# LB1_Expansion_Board.net
KiCad netlist of a schematic drawn in EAGLE
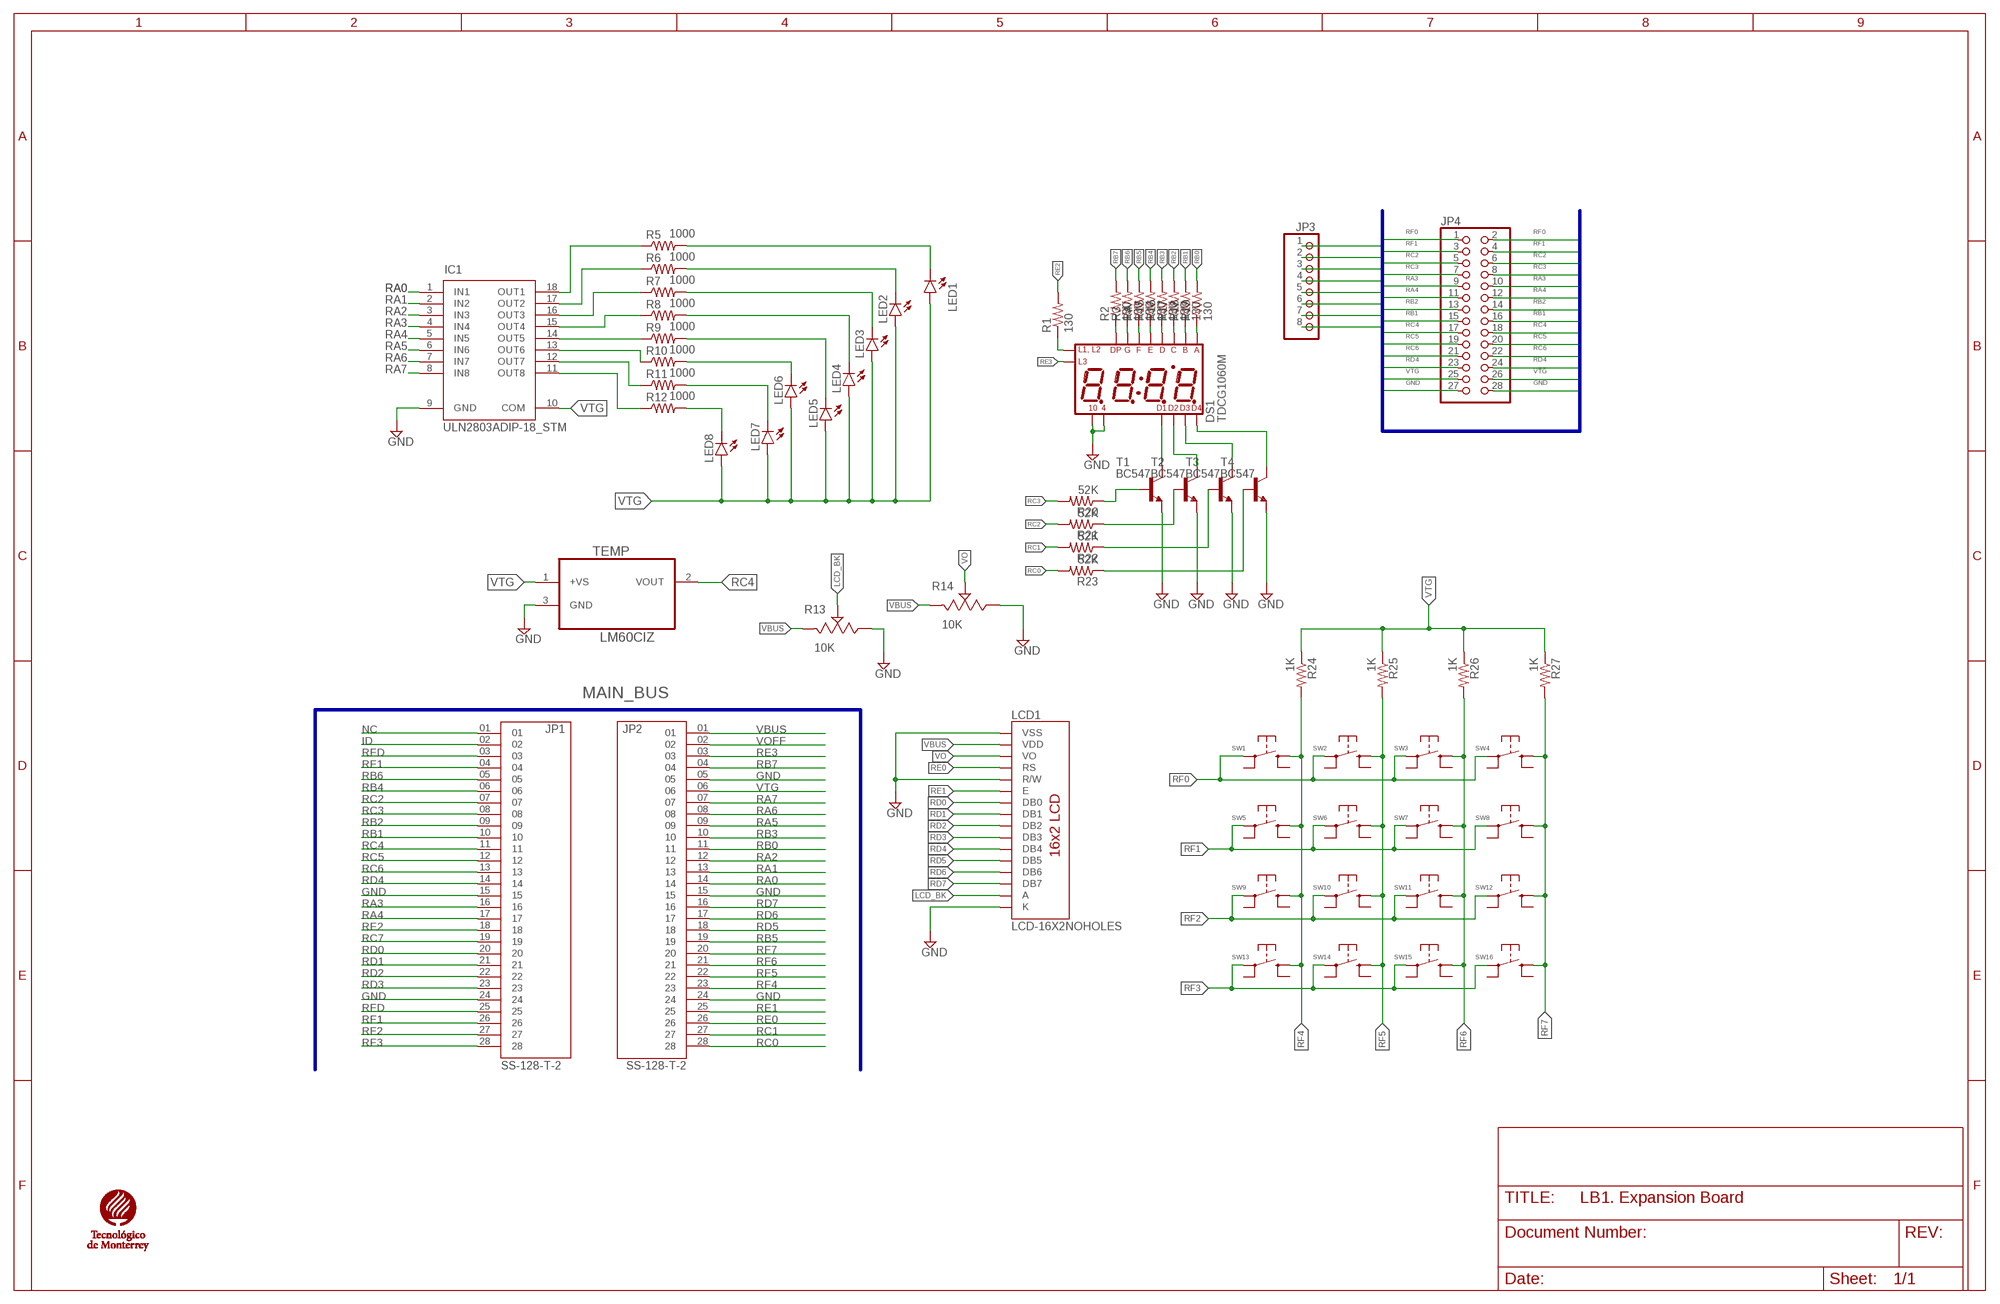
[diagram p0: schematic, sheet 1]

(export (version "E")
  (design (tool "Eeschema 10.0.6"))
  (components
    (comp (ref "DS1")
      (value "TDCG1060M")
      (footprint "eagle-import:DISPLAY_TDCG1060M")
      (fields (field (name "DIGI-KEY_PART_NUMBER") "TDCG1060M-ND") (field (name "MF") "Vishay"))
      (libsource (lib "eagle-import") (part "TDCG1060M"))
    )
    (comp (ref "IC1")
      (value "ULN2803ADIP-18_STM")
      (footprint "eagle-import:DIP-18_STM")
      (fields
        (field (name "MANUFACTURER_PART_NUMBER") "ULN2803A")
        (field (name "COPYRIGHT") "Copyright (C) 2022 Ultra Librarian. All rights reserved.")
      )
      (libsource (lib "eagle-import") (part "ULN2803ADIP-18_STM"))
    )
    (comp (ref "JP1")
      (value "SS-128-T-2")
      (footprint "eagle-import:SAMTEC_SS-128-T-2")
      (fields (field (name "DIGI-KEY_PART_NUMBER") "SAM1117-28-ND") (field (name "MF") "Samtec"))
      (libsource (lib "eagle-import") (part "SS-128-T-2"))
    )
    (comp (ref "JP2")
      (value "SS-128-T-2")
      (footprint "eagle-import:SAMTEC_SS-128-T-2")
      (fields (field (name "DIGI-KEY_PART_NUMBER") "SAM1117-28-ND") (field (name "MF") "Samtec"))
      (libsource (lib "eagle-import") (part "SS-128-T-2"))
    )
    (comp (ref "JP3")
      (value "PINHD-1X8BIG")
      (footprint "eagle-import:1X08-BIG")
      (libsource (lib "eagle-import") (part "PINHD-1X8BIG"))
    )
    (comp (ref "JP4")
      (value "PINHD-2X14-CB")
      (footprint "eagle-import:2X14-BIG")
      (libsource (lib "eagle-import") (part "PINHD-2X14-CB"))
    )
    (comp (ref "LCD1")
      (value "LCD-16X2NOHOLES")
      (footprint "eagle-import:LCD-16X2_NOHOLESNOSILK")
      (libsource (lib "eagle-import") (part "LCD-16X2NOHOLES"))
    )
    (comp (ref "LED1")
      (value "LED3MM")
      (footprint "eagle-import:LED3MM")
      (libsource (lib "eagle-import") (part "LED3MM"))
    )
    (comp (ref "LED2")
      (value "LED3MM")
      (footprint "eagle-import:LED3MM")
      (libsource (lib "eagle-import") (part "LED3MM"))
    )
    (comp (ref "LED3")
      (value "LED3MM")
      (footprint "eagle-import:LED3MM")
      (libsource (lib "eagle-import") (part "LED3MM"))
    )
    (comp (ref "LED4")
      (value "LED3MM")
      (footprint "eagle-import:LED3MM")
      (libsource (lib "eagle-import") (part "LED3MM"))
    )
    (comp (ref "LED5")
      (value "LED3MM")
      (footprint "eagle-import:LED3MM")
      (libsource (lib "eagle-import") (part "LED3MM"))
    )
    (comp (ref "LED6")
      (value "LED3MM")
      (footprint "eagle-import:LED3MM")
      (libsource (lib "eagle-import") (part "LED3MM"))
    )
    (comp (ref "LED7")
      (value "LED3MM")
      (footprint "eagle-import:LED3MM")
      (libsource (lib "eagle-import") (part "LED3MM"))
    )
    (comp (ref "LED8")
      (value "LED3MM")
      (footprint "eagle-import:LED3MM")
      (libsource (lib "eagle-import") (part "LED3MM"))
    )
    (comp (ref "R1")
      (value "130")
      (footprint "eagle-import:0207_10")
      (libsource (lib "eagle-import") (part "R-US"))
    )
    (comp (ref "R2")
      (value "130")
      (footprint "eagle-import:0207_10")
      (libsource (lib "eagle-import") (part "R-US"))
    )
    (comp (ref "R3")
      (value "130")
      (footprint "eagle-import:0207_10")
      (libsource (lib "eagle-import") (part "R-US"))
    )
    (comp (ref "R4")
      (value "130")
      (footprint "eagle-import:0207_10")
      (libsource (lib "eagle-import") (part "R-US"))
    )
    (comp (ref "R5")
      (value "1000")
      (footprint "eagle-import:0207_10")
      (libsource (lib "eagle-import") (part "R-US"))
    )
    (comp (ref "R6")
      (value "1000")
      (footprint "eagle-import:0207_10")
      (libsource (lib "eagle-import") (part "R-US"))
    )
    (comp (ref "R7")
      (value "1000")
      (footprint "eagle-import:0207_10")
      (libsource (lib "eagle-import") (part "R-US"))
    )
    (comp (ref "R8")
      (value "1000")
      (footprint "eagle-import:0207_10")
      (libsource (lib "eagle-import") (part "R-US"))
    )
    (comp (ref "R9")
      (value "1000")
      (footprint "eagle-import:0207_10")
      (libsource (lib "eagle-import") (part "R-US"))
    )
    (comp (ref "R10")
      (value "1000")
      (footprint "eagle-import:0207_10")
      (libsource (lib "eagle-import") (part "R-US"))
    )
    (comp (ref "R11")
      (value "1000")
      (footprint "eagle-import:0207_10")
      (libsource (lib "eagle-import") (part "R-US"))
    )
    (comp (ref "R12")
      (value "1000")
      (footprint "eagle-import:0207_10")
      (libsource (lib "eagle-import") (part "R-US"))
    )
    (comp (ref "R13")
      (value "10K")
      (footprint "eagle-import:3362P-1-103LF")
      (fields
        (field (name "MANUFACTURER") "Bourns Inc.")
        (field (name "MPN") "3362P-1-103LF")
        (field (name "CREATED_PN") "PCBLayout.com")
      )
      (libsource (lib "eagle-import") (part "3362P-1-103LF"))
    )
    (comp (ref "R14")
      (value "10K")
      (footprint "eagle-import:3362P-1-103LF")
      (fields
        (field (name "MANUFACTURER") "Bourns Inc.")
        (field (name "MPN") "3362P-1-103LF")
        (field (name "CREATED_PN") "PCBLayout.com")
      )
      (libsource (lib "eagle-import") (part "3362P-1-103LF"))
    )
    (comp (ref "R15")
      (value "130")
      (footprint "eagle-import:0207_10")
      (libsource (lib "eagle-import") (part "R-US"))
    )
    (comp (ref "R16")
      (value "130")
      (footprint "eagle-import:0207_10")
      (libsource (lib "eagle-import") (part "R-US"))
    )
    (comp (ref "R17")
      (value "130")
      (footprint "eagle-import:0207_10")
      (libsource (lib "eagle-import") (part "R-US"))
    )
    (comp (ref "R18")
      (value "130")
      (footprint "eagle-import:0207_10")
      (libsource (lib "eagle-import") (part "R-US"))
    )
    (comp (ref "R19")
      (value "130")
      (footprint "eagle-import:0207_10")
      (libsource (lib "eagle-import") (part "R-US"))
    )
    (comp (ref "R20")
      (value "52K")
      (footprint "eagle-import:0207_10")
      (libsource (lib "eagle-import") (part "R-US"))
    )
    (comp (ref "R21")
      (value "52K")
      (footprint "eagle-import:0207_10")
      (libsource (lib "eagle-import") (part "R-US"))
    )
    (comp (ref "R22")
      (value "52K")
      (footprint "eagle-import:0207_10")
      (libsource (lib "eagle-import") (part "R-US"))
    )
    (comp (ref "R23")
      (value "52K")
      (footprint "eagle-import:0207_10")
      (libsource (lib "eagle-import") (part "R-US"))
    )
    (comp (ref "R24")
      (value "1K")
      (footprint "eagle-import:0207_10")
      (libsource (lib "eagle-import") (part "R-US"))
    )
    (comp (ref "R25")
      (value "1K")
      (footprint "eagle-import:0207_10")
      (libsource (lib "eagle-import") (part "R-US"))
    )
    (comp (ref "R26")
      (value "1K")
      (footprint "eagle-import:0207_10")
      (libsource (lib "eagle-import") (part "R-US"))
    )
    (comp (ref "R27")
      (value "1K")
      (footprint "eagle-import:0207_10")
      (libsource (lib "eagle-import") (part "R-US"))
    )
    (comp (ref "SW1")
      (value "1825910-2")
      (footprint "eagle-import:TE_1825910-2")
      (fields (field (name "MF") "TE Connectivity"))
      (libsource (lib "eagle-import") (part "1825910-2"))
    )
    (comp (ref "SW2")
      (value "1825910-2")
      (footprint "eagle-import:TE_1825910-2")
      (fields (field (name "MF") "TE Connectivity"))
      (libsource (lib "eagle-import") (part "1825910-2"))
    )
    (comp (ref "SW3")
      (value "1825910-2")
      (footprint "eagle-import:TE_1825910-2")
      (fields (field (name "MF") "TE Connectivity"))
      (libsource (lib "eagle-import") (part "1825910-2"))
    )
    (comp (ref "SW4")
      (value "1825910-2")
      (footprint "eagle-import:TE_1825910-2")
      (fields (field (name "MF") "TE Connectivity"))
      (libsource (lib "eagle-import") (part "1825910-2"))
    )
    (comp (ref "SW5")
      (value "1825910-2")
      (footprint "eagle-import:TE_1825910-2")
      (fields (field (name "MF") "TE Connectivity"))
      (libsource (lib "eagle-import") (part "1825910-2"))
    )
    (comp (ref "SW6")
      (value "1825910-2")
      (footprint "eagle-import:TE_1825910-2")
      (fields (field (name "MF") "TE Connectivity"))
      (libsource (lib "eagle-import") (part "1825910-2"))
    )
    (comp (ref "SW7")
      (value "1825910-2")
      (footprint "eagle-import:TE_1825910-2")
      (fields (field (name "MF") "TE Connectivity"))
      (libsource (lib "eagle-import") (part "1825910-2"))
    )
    (comp (ref "SW8")
      (value "1825910-2")
      (footprint "eagle-import:TE_1825910-2")
      (fields (field (name "MF") "TE Connectivity"))
      (libsource (lib "eagle-import") (part "1825910-2"))
    )
    (comp (ref "SW9")
      (value "1825910-2")
      (footprint "eagle-import:TE_1825910-2")
      (fields (field (name "MF") "TE Connectivity"))
      (libsource (lib "eagle-import") (part "1825910-2"))
    )
    (comp (ref "SW10")
      (value "1825910-2")
      (footprint "eagle-import:TE_1825910-2")
      (fields (field (name "MF") "TE Connectivity"))
      (libsource (lib "eagle-import") (part "1825910-2"))
    )
    (comp (ref "SW11")
      (value "1825910-2")
      (footprint "eagle-import:TE_1825910-2")
      (fields (field (name "MF") "TE Connectivity"))
      (libsource (lib "eagle-import") (part "1825910-2"))
    )
    (comp (ref "SW12")
      (value "1825910-2")
      (footprint "eagle-import:TE_1825910-2")
      (fields (field (name "MF") "TE Connectivity"))
      (libsource (lib "eagle-import") (part "1825910-2"))
    )
    (comp (ref "SW13")
      (value "1825910-2")
      (footprint "eagle-import:TE_1825910-2")
      (fields (field (name "MF") "TE Connectivity"))
      (libsource (lib "eagle-import") (part "1825910-2"))
    )
    (comp (ref "SW14")
      (value "1825910-2")
      (footprint "eagle-import:TE_1825910-2")
      (fields (field (name "MF") "TE Connectivity"))
      (libsource (lib "eagle-import") (part "1825910-2"))
    )
    (comp (ref "SW15")
      (value "1825910-2")
      (footprint "eagle-import:TE_1825910-2")
      (fields (field (name "MF") "TE Connectivity"))
      (libsource (lib "eagle-import") (part "1825910-2"))
    )
    (comp (ref "SW16")
      (value "1825910-2")
      (footprint "eagle-import:TE_1825910-2")
      (fields (field (name "MF") "TE Connectivity"))
      (libsource (lib "eagle-import") (part "1825910-2"))
    )
    (comp (ref "T1")
      (value "BC547")
      (footprint "eagle-import:TO92")
      (libsource (lib "eagle-import") (part "BC547"))
    )
    (comp (ref "T2")
      (value "BC547")
      (footprint "eagle-import:TO92")
      (libsource (lib "eagle-import") (part "BC547"))
    )
    (comp (ref "T3")
      (value "BC547")
      (footprint "eagle-import:TO92")
      (libsource (lib "eagle-import") (part "BC547"))
    )
    (comp (ref "T4")
      (value "BC547")
      (footprint "eagle-import:TO92")
      (libsource (lib "eagle-import") (part "BC547"))
    )
    (comp (ref "TEC1")
      (value "TEC_LOGO")
      (footprint "eagle-import:TEC_LOGO")
      (libsource (lib "eagle-import") (part "TEC_LOGO"))
    )
    (comp (ref "TEMP")
      (value "LM60CIZ")
      (footprint "eagle-import:TO92_")
      (libsource (lib "eagle-import") (part "LM60CIZ"))
    )
  )
  (nets
    (net (code "2") (name "/ID") (class "Default")
      (node (ref "JP1") (pin "02") (pinfunction "02_02") (pintype "passive"))
    )
    (net (code "3") (name "/NC") (class "Default")
      (node (ref "JP1") (pin "01") (pinfunction "01_01") (pintype "passive"))
    )
    (net (code "4") (name "/RA0") (class "Default")
      (node (ref "IC1") (pin "1") (pinfunction "IN1_1") (pintype "input"))
      (node (ref "JP2") (pin "14") (pinfunction "14_14") (pintype "passive"))
    )
    (net (code "5") (name "/RA1") (class "Default")
      (node (ref "IC1") (pin "2") (pinfunction "IN2_2") (pintype "input"))
      (node (ref "JP2") (pin "13") (pinfunction "13_13") (pintype "passive"))
    )
    (net (code "6") (name "/RA2") (class "Default")
      (node (ref "IC1") (pin "3") (pinfunction "IN3_3") (pintype "input"))
      (node (ref "JP2") (pin "12") (pinfunction "12_12") (pintype "passive"))
    )
    (net (code "7") (name "/RA3") (class "Default")
      (node (ref "IC1") (pin "4") (pinfunction "IN4_4") (pintype "input"))
      (node (ref "JP1") (pin "16") (pinfunction "16_16") (pintype "passive"))
      (node (ref "JP3") (pin "2") (pinfunction "2_2") (pintype "passive"))
      (node (ref "JP4") (pin "10") (pinfunction "10_10") (pintype "passive"))
      (node (ref "JP4") (pin "9") (pinfunction "9_9") (pintype "passive"))
    )
    (net (code "8") (name "/RA4") (class "Default")
      (node (ref "IC1") (pin "5") (pinfunction "IN5_5") (pintype "input"))
      (node (ref "JP1") (pin "17") (pinfunction "17_17") (pintype "passive"))
      (node (ref "JP3") (pin "3") (pinfunction "3_3") (pintype "passive"))
      (node (ref "JP4") (pin "11") (pinfunction "11_11") (pintype "passive"))
      (node (ref "JP4") (pin "12") (pinfunction "12_12") (pintype "passive"))
    )
    (net (code "9") (name "/RA5") (class "Default")
      (node (ref "IC1") (pin "6") (pinfunction "IN6_6") (pintype "input"))
      (node (ref "JP2") (pin "09") (pinfunction "09_09") (pintype "passive"))
    )
    (net (code "10") (name "/RA6") (class "Default")
      (node (ref "IC1") (pin "7") (pinfunction "IN7_7") (pintype "input"))
      (node (ref "JP2") (pin "08") (pinfunction "08_08") (pintype "passive"))
    )
    (net (code "11") (name "/RA7") (class "Default")
      (node (ref "IC1") (pin "8") (pinfunction "IN8_8") (pintype "input"))
      (node (ref "JP2") (pin "07") (pinfunction "07_07") (pintype "passive"))
    )
    (net (code "12") (name "/RC5") (class "Default")
      (node (ref "JP1") (pin "12") (pinfunction "12_12") (pintype "passive"))
      (node (ref "JP4") (pin "19") (pinfunction "19_19") (pintype "passive"))
      (node (ref "JP4") (pin "20") (pinfunction "20_20") (pintype "passive"))
    )
    (net (code "13") (name "/RC6") (class "Default")
      (node (ref "JP1") (pin "13") (pinfunction "13_13") (pintype "passive"))
      (node (ref "JP4") (pin "21") (pinfunction "21_21") (pintype "passive"))
      (node (ref "JP4") (pin "22") (pinfunction "22_22") (pintype "passive"))
    )
    (net (code "14") (name "/RC7") (class "Default")
      (node (ref "JP1") (pin "19") (pinfunction "19_19") (pintype "passive"))
    )
    (net (code "15") (name "/RFD") (class "Default")
      (node (ref "JP1") (pin "03") (pinfunction "03_03") (pintype "passive"))
      (node (ref "JP1") (pin "25") (pinfunction "25_25") (pintype "passive"))
    )
    (net (code "16") (name "/VOFF") (class "Default")
      (node (ref "JP2") (pin "02") (pinfunction "02_02") (pintype "passive"))
    )
    (net (code "18") (name "GND") (class "Default")
      (node (ref "DS1") (pin "10") (pinfunction "10_10") (pintype "passive"))
      (node (ref "DS1") (pin "4") (pinfunction "4_4") (pintype "passive"))
      (node (ref "IC1") (pin "9") (pinfunction "GND_9") (pintype "power_in"))
      (node (ref "JP1") (pin "15") (pinfunction "15_15") (pintype "passive"))
      (node (ref "JP1") (pin "24") (pinfunction "24_24") (pintype "passive"))
      (node (ref "JP2") (pin "05") (pinfunction "05_05") (pintype "passive"))
      (node (ref "JP2") (pin "15") (pinfunction "15_15") (pintype "passive"))
      (node (ref "JP2") (pin "24") (pinfunction "24_24") (pintype "passive"))
      (node (ref "JP3") (pin "1") (pinfunction "1_1") (pintype "passive"))
      (node (ref "JP4") (pin "27") (pinfunction "27_27") (pintype "passive"))
      (node (ref "JP4") (pin "28") (pinfunction "28_28") (pintype "passive"))
      (node (ref "LCD1") (pin "1") (pinfunction "VSS_1") (pintype "power_in"))
      (node (ref "LCD1") (pin "16") (pinfunction "K_16") (pintype "power_in"))
      (node (ref "LCD1") (pin "5") (pinfunction "R/W_5") (pintype "input"))
      (node (ref "R13") (pin "3") (pinfunction "3_3") (pintype "passive"))
      (node (ref "R14") (pin "3") (pinfunction "3_3") (pintype "passive"))
      (node (ref "T1") (pin "1") (pinfunction "E_1") (pintype "passive"))
      (node (ref "T2") (pin "1") (pinfunction "E_1") (pintype "passive"))
      (node (ref "T3") (pin "1") (pinfunction "E_1") (pintype "passive"))
      (node (ref "T4") (pin "1") (pinfunction "E_1") (pintype "passive"))
      (node (ref "TEMP") (pin "3") (pinfunction "GND_3") (pintype "passive"))
    )
    (net (code "19") (name "LCD_BK") (class "Default")
      (node (ref "LCD1") (pin "15") (pinfunction "A_15") (pintype "power_in"))
      (node (ref "R13") (pin "2") (pinfunction "2_2") (pintype "passive"))
    )
    (net (code "20") (name "Net-(DS1-A)") (class "Default")
      (node (ref "DS1") (pin "14") (pinfunction "A_14") (pintype "passive"))
      (node (ref "R19") (pin "1") (pinfunction "1_1") (pintype "passive"))
    )
    (net (code "21") (name "Net-(DS1-B)") (class "Default")
      (node (ref "DS1") (pin "16") (pinfunction "B_16") (pintype "passive"))
      (node (ref "R18") (pin "1") (pinfunction "1_1") (pintype "passive"))
    )
    (net (code "22") (name "Net-(DS1-C)") (class "Default")
      (node (ref "DS1") (pin "13") (pinfunction "C_13") (pintype "passive"))
      (node (ref "R17") (pin "1") (pinfunction "1_1") (pintype "passive"))
    )
    (net (code "23") (name "Net-(DS1-D)") (class "Default")
      (node (ref "DS1") (pin "3") (pinfunction "D_3") (pintype "passive"))
      (node (ref "R16") (pin "1") (pinfunction "1_1") (pintype "passive"))
    )
    (net (code "24") (name "Net-(DS1-DIG1)") (class "Default")
      (node (ref "DS1") (pin "1") (pinfunction "DIG1_1") (pintype "passive"))
      (node (ref "T1") (pin "3") (pinfunction "C_3") (pintype "passive"))
    )
    (net (code "25") (name "Net-(DS1-DIG2)") (class "Default")
      (node (ref "DS1") (pin "2") (pinfunction "DIG2_2") (pintype "passive"))
      (node (ref "T2") (pin "3") (pinfunction "C_3") (pintype "passive"))
    )
    (net (code "26") (name "Net-(DS1-DIG3)") (class "Default")
      (node (ref "DS1") (pin "6") (pinfunction "DIG3_6") (pintype "passive"))
      (node (ref "T3") (pin "3") (pinfunction "C_3") (pintype "passive"))
    )
    (net (code "27") (name "Net-(DS1-DIG4)") (class "Default")
      (node (ref "DS1") (pin "8") (pinfunction "DIG4_8") (pintype "passive"))
      (node (ref "T4") (pin "3") (pinfunction "C_3") (pintype "passive"))
    )
    (net (code "28") (name "Net-(DS1-DP)") (class "Default")
      (node (ref "DS1") (pin "7") (pinfunction "DP_7") (pintype "passive"))
      (node (ref "R2") (pin "1") (pinfunction "1_1") (pintype "passive"))
    )
    (net (code "29") (name "Net-(DS1-E)") (class "Default")
      (node (ref "DS1") (pin "5") (pinfunction "E_5") (pintype "passive"))
      (node (ref "R15") (pin "1") (pinfunction "1_1") (pintype "passive"))
    )
    (net (code "30") (name "Net-(DS1-F)") (class "Default")
      (node (ref "DS1") (pin "11") (pinfunction "F_11") (pintype "passive"))
      (node (ref "R4") (pin "1") (pinfunction "1_1") (pintype "passive"))
    )
    (net (code "31") (name "Net-(DS1-G)") (class "Default")
      (node (ref "DS1") (pin "15") (pinfunction "G_15") (pintype "passive"))
      (node (ref "R3") (pin "1") (pinfunction "1_1") (pintype "passive"))
    )
    (net (code "32") (name "Net-(DS1-L1_L2)") (class "Default")
      (node (ref "DS1") (pin "12") (pinfunction "L1_L2_12") (pintype "passive"))
      (node (ref "R1") (pin "1") (pinfunction "1_1") (pintype "passive"))
    )
    (net (code "33") (name "Net-(IC1-OUT1)") (class "Default")
      (node (ref "IC1") (pin "18") (pinfunction "OUT1_18") (pintype "passive"))
      (node (ref "R5") (pin "1") (pinfunction "1_1") (pintype "passive"))
    )
    (net (code "34") (name "Net-(IC1-OUT2)") (class "Default")
      (node (ref "IC1") (pin "17") (pinfunction "OUT2_17") (pintype "passive"))
      (node (ref "R6") (pin "1") (pinfunction "1_1") (pintype "passive"))
    )
    (net (code "35") (name "Net-(IC1-OUT3)") (class "Default")
      (node (ref "IC1") (pin "16") (pinfunction "OUT3_16") (pintype "passive"))
      (node (ref "R7") (pin "1") (pinfunction "1_1") (pintype "passive"))
    )
    (net (code "36") (name "Net-(IC1-OUT4)") (class "Default")
      (node (ref "IC1") (pin "15") (pinfunction "OUT4_15") (pintype "passive"))
      (node (ref "R8") (pin "1") (pinfunction "1_1") (pintype "passive"))
    )
    (net (code "37") (name "Net-(IC1-OUT5)") (class "Default")
      (node (ref "IC1") (pin "14") (pinfunction "OUT5_14") (pintype "passive"))
      (node (ref "R9") (pin "1") (pinfunction "1_1") (pintype "passive"))
    )
    (net (code "38") (name "Net-(IC1-OUT6)") (class "Default")
      (node (ref "IC1") (pin "13") (pinfunction "OUT6_13") (pintype "passive"))
      (node (ref "R10") (pin "1") (pinfunction "1_1") (pintype "passive"))
    )
    (net (code "39") (name "Net-(IC1-OUT7)") (class "Default")
      (node (ref "IC1") (pin "12") (pinfunction "OUT7_12") (pintype "passive"))
      (node (ref "R11") (pin "1") (pinfunction "1_1") (pintype "passive"))
    )
    (net (code "40") (name "Net-(IC1-OUT8)") (class "Default")
      (node (ref "IC1") (pin "11") (pinfunction "OUT8_11") (pintype "passive"))
      (node (ref "R12") (pin "1") (pinfunction "1_1") (pintype "passive"))
    )
    (net (code "41") (name "Net-(LED1-C)") (class "Default")
      (node (ref "LED1") (pin "K") (pinfunction "C_K") (pintype "passive"))
      (node (ref "R5") (pin "2") (pinfunction "2_2") (pintype "passive"))
    )
    (net (code "42") (name "Net-(LED1-PadA)") (class "Default")
      (node (ref "LED1") (pin "A") (pinfunction "A_A") (pintype "passive"))
      (node (ref "LED2") (pin "A") (pinfunction "A_A") (pintype "passive"))
      (node (ref "LED3") (pin "A") (pinfunction "A_A") (pintype "passive"))
      (node (ref "LED4") (pin "A") (pinfunction "A_A") (pintype "passive"))
      (node (ref "LED5") (pin "A") (pinfunction "A_A") (pintype "passive"))
      (node (ref "LED6") (pin "A") (pinfunction "A_A") (pintype "passive"))
      (node (ref "LED7") (pin "A") (pinfunction "A_A") (pintype "passive"))
      (node (ref "LED8") (pin "A") (pinfunction "A_A") (pintype "passive"))
    )
    (net (code "43") (name "Net-(LED2-C)") (class "Default")
      (node (ref "LED2") (pin "K") (pinfunction "C_K") (pintype "passive"))
      (node (ref "R6") (pin "2") (pinfunction "2_2") (pintype "passive"))
    )
    (net (code "44") (name "Net-(LED3-C)") (class "Default")
      (node (ref "LED3") (pin "K") (pinfunction "C_K") (pintype "passive"))
      (node (ref "R7") (pin "2") (pinfunction "2_2") (pintype "passive"))
    )
    (net (code "45") (name "Net-(LED4-C)") (class "Default")
      (node (ref "LED4") (pin "K") (pinfunction "C_K") (pintype "passive"))
      (node (ref "R8") (pin "2") (pinfunction "2_2") (pintype "passive"))
    )
    (net (code "46") (name "Net-(LED5-C)") (class "Default")
      (node (ref "LED5") (pin "K") (pinfunction "C_K") (pintype "passive"))
      (node (ref "R9") (pin "2") (pinfunction "2_2") (pintype "passive"))
    )
    (net (code "47") (name "Net-(LED6-C)") (class "Default")
      (node (ref "LED6") (pin "K") (pinfunction "C_K") (pintype "passive"))
      (node (ref "R10") (pin "2") (pinfunction "2_2") (pintype "passive"))
    )
    (net (code "48") (name "Net-(LED7-C)") (class "Default")
      (node (ref "LED7") (pin "K") (pinfunction "C_K") (pintype "passive"))
      (node (ref "R11") (pin "2") (pinfunction "2_2") (pintype "passive"))
    )
    (net (code "49") (name "Net-(LED8-C)") (class "Default")
      (node (ref "LED8") (pin "K") (pinfunction "C_K") (pintype "passive"))
      (node (ref "R12") (pin "2") (pinfunction "2_2") (pintype "passive"))
    )
    (net (code "50") (name "Net-(T1-B)") (class "Default")
      (node (ref "R20") (pin "1") (pinfunction "1_1") (pintype "passive"))
      (node (ref "T1") (pin "2") (pinfunction "B_2") (pintype "passive"))
    )
    (net (code "51") (name "Net-(T2-B)") (class "Default")
      (node (ref "R21") (pin "1") (pinfunction "1_1") (pintype "passive"))
      (node (ref "T2") (pin "2") (pinfunction "B_2") (pintype "passive"))
    )
    (net (code "52") (name "Net-(T3-B)") (class "Default")
      (node (ref "R22") (pin "1") (pinfunction "1_1") (pintype "passive"))
      (node (ref "T3") (pin "2") (pinfunction "B_2") (pintype "passive"))
    )
    (net (code "53") (name "Net-(T4-B)") (class "Default")
      (node (ref "R23") (pin "1") (pinfunction "1_1") (pintype "passive"))
      (node (ref "T4") (pin "2") (pinfunction "B_2") (pintype "passive"))
    )
    (net (code "54") (name "RB0") (class "Default")
      (node (ref "JP2") (pin "11") (pinfunction "11_11") (pintype "passive"))
      (node (ref "R19") (pin "2") (pinfunction "2_2") (pintype "passive"))
    )
    (net (code "55") (name "RB1") (class "Default")
      (node (ref "JP1") (pin "10") (pinfunction "10_10") (pintype "passive"))
      (node (ref "JP3") (pin "4") (pinfunction "4_4") (pintype "passive"))
      (node (ref "JP4") (pin "15") (pinfunction "15_15") (pintype "passive"))
      (node (ref "JP4") (pin "16") (pinfunction "16_16") (pintype "passive"))
      (node (ref "R18") (pin "2") (pinfunction "2_2") (pintype "passive"))
    )
    (net (code "56") (name "RB2") (class "Default")
      (node (ref "JP1") (pin "09") (pinfunction "09_09") (pintype "passive"))
      (node (ref "JP3") (pin "5") (pinfunction "5_5") (pintype "passive"))
      (node (ref "JP4") (pin "13") (pinfunction "13_13") (pintype "passive"))
      (node (ref "JP4") (pin "14") (pinfunction "14_14") (pintype "passive"))
      (node (ref "R17") (pin "2") (pinfunction "2_2") (pintype "passive"))
    )
    (net (code "57") (name "RB3") (class "Default")
      (node (ref "JP2") (pin "10") (pinfunction "10_10") (pintype "passive"))
      (node (ref "R16") (pin "2") (pinfunction "2_2") (pintype "passive"))
    )
    (net (code "58") (name "RB4") (class "Default")
      (node (ref "JP1") (pin "06") (pinfunction "06_06") (pintype "passive"))
      (node (ref "R15") (pin "2") (pinfunction "2_2") (pintype "passive"))
    )
    (net (code "59") (name "RB5") (class "Default")
      (node (ref "JP2") (pin "19") (pinfunction "19_19") (pintype "passive"))
      (node (ref "R4") (pin "2") (pinfunction "2_2") (pintype "passive"))
    )
    (net (code "60") (name "RB6") (class "Default")
      (node (ref "JP1") (pin "05") (pinfunction "05_05") (pintype "passive"))
      (node (ref "R3") (pin "2") (pinfunction "2_2") (pintype "passive"))
    )
    (net (code "61") (name "RB7") (class "Default")
      (node (ref "JP2") (pin "04") (pinfunction "04_04") (pintype "passive"))
      (node (ref "R2") (pin "2") (pinfunction "2_2") (pintype "passive"))
    )
    (net (code "62") (name "RC0") (class "Default")
      (node (ref "JP2") (pin "28") (pinfunction "28_28") (pintype "passive"))
      (node (ref "R23") (pin "2") (pinfunction "2_2") (pintype "passive"))
    )
    (net (code "63") (name "RC1") (class "Default")
      (node (ref "JP2") (pin "27") (pinfunction "27_27") (pintype "passive"))
      (node (ref "R22") (pin "2") (pinfunction "2_2") (pintype "passive"))
    )
    (net (code "64") (name "RC2") (class "Default")
      (node (ref "JP1") (pin "07") (pinfunction "07_07") (pintype "passive"))
      (node (ref "JP3") (pin "6") (pinfunction "6_6") (pintype "passive"))
      (node (ref "JP4") (pin "5") (pinfunction "5_5") (pintype "passive"))
      (node (ref "JP4") (pin "6") (pinfunction "6_6") (pintype "passive"))
      (node (ref "R21") (pin "2") (pinfunction "2_2") (pintype "passive"))
    )
    (net (code "65") (name "RC3") (class "Default")
      (node (ref "JP1") (pin "08") (pinfunction "08_08") (pintype "passive"))
      (node (ref "JP3") (pin "7") (pinfunction "7_7") (pintype "passive"))
      (node (ref "JP4") (pin "7") (pinfunction "7_7") (pintype "passive"))
      (node (ref "JP4") (pin "8") (pinfunction "8_8") (pintype "passive"))
      (node (ref "R20") (pin "2") (pinfunction "2_2") (pintype "passive"))
    )
    (net (code "66") (name "RC4") (class "Default")
      (node (ref "JP1") (pin "11") (pinfunction "11_11") (pintype "passive"))
      (node (ref "JP3") (pin "8") (pinfunction "8_8") (pintype "passive"))
      (node (ref "JP4") (pin "17") (pinfunction "17_17") (pintype "passive"))
      (node (ref "JP4") (pin "18") (pinfunction "18_18") (pintype "passive"))
      (node (ref "TEMP") (pin "2") (pinfunction "VOUT_2") (pintype "output"))
    )
    (net (code "67") (name "RD0") (class "Default")
      (node (ref "JP1") (pin "20") (pinfunction "20_20") (pintype "passive"))
      (node (ref "LCD1") (pin "7") (pinfunction "DB0_7") (pintype "bidirectional"))
    )
    (net (code "68") (name "RD1") (class "Default")
      (node (ref "JP1") (pin "21") (pinfunction "21_21") (pintype "passive"))
      (node (ref "LCD1") (pin "8") (pinfunction "DB1_8") (pintype "bidirectional"))
    )
    (net (code "69") (name "RD2") (class "Default")
      (node (ref "JP1") (pin "22") (pinfunction "22_22") (pintype "passive"))
      (node (ref "LCD1") (pin "9") (pinfunction "DB2_9") (pintype "bidirectional"))
    )
    (net (code "70") (name "RD3") (class "Default")
      (node (ref "JP1") (pin "23") (pinfunction "23_23") (pintype "passive"))
      (node (ref "LCD1") (pin "10") (pinfunction "DB3_10") (pintype "bidirectional"))
    )
    (net (code "71") (name "RD4") (class "Default")
      (node (ref "JP1") (pin "14") (pinfunction "14_14") (pintype "passive"))
      (node (ref "JP4") (pin "23") (pinfunction "23_23") (pintype "passive"))
      (node (ref "JP4") (pin "24") (pinfunction "24_24") (pintype "passive"))
      (node (ref "LCD1") (pin "11") (pinfunction "DB4_11") (pintype "bidirectional"))
    )
    (net (code "72") (name "RD5") (class "Default")
      (node (ref "JP2") (pin "18") (pinfunction "18_18") (pintype "passive"))
      (node (ref "LCD1") (pin "12") (pinfunction "DB5_12") (pintype "bidirectional"))
    )
    (net (code "73") (name "RD6") (class "Default")
      (node (ref "JP2") (pin "17") (pinfunction "17_17") (pintype "passive"))
      (node (ref "LCD1") (pin "13") (pinfunction "DB6_13") (pintype "bidirectional"))
    )
    (net (code "74") (name "RD7") (class "Default")
      (node (ref "JP2") (pin "16") (pinfunction "16_16") (pintype "passive"))
      (node (ref "LCD1") (pin "14") (pinfunction "DB7_14") (pintype "bidirectional"))
    )
    (net (code "75") (name "RE0") (class "Default")
      (node (ref "JP2") (pin "26") (pinfunction "26_26") (pintype "passive"))
      (node (ref "LCD1") (pin "4") (pinfunction "RS_4") (pintype "input"))
    )
    (net (code "76") (name "RE1") (class "Default")
      (node (ref "JP2") (pin "25") (pinfunction "25_25") (pintype "passive"))
      (node (ref "LCD1") (pin "6") (pinfunction "E_6") (pintype "input"))
    )
    (net (code "77") (name "RE2") (class "Default")
      (node (ref "JP1") (pin "18") (pinfunction "18_18") (pintype "passive"))
      (node (ref "R1") (pin "2") (pinfunction "2_2") (pintype "passive"))
    )
    (net (code "78") (name "RE3") (class "Default")
      (node (ref "DS1") (pin "9") (pinfunction "L3_9") (pintype "passive"))
      (node (ref "JP2") (pin "03") (pinfunction "03_03") (pintype "passive"))
    )
    (net (code "79") (name "RF0") (class "Default")
      (node (ref "JP4") (pin "1") (pinfunction "1_1") (pintype "passive"))
      (node (ref "JP4") (pin "2") (pinfunction "2_2") (pintype "passive"))
      (node (ref "SW1") (pin "1") (pinfunction "P_1") (pintype "passive"))
      (node (ref "SW2") (pin "1") (pinfunction "P_1") (pintype "passive"))
      (node (ref "SW3") (pin "1") (pinfunction "P_1") (pintype "passive"))
      (node (ref "SW4") (pin "1") (pinfunction "P_1") (pintype "passive"))
    )
    (net (code "80") (name "RF1") (class "Default")
      (node (ref "JP1") (pin "04") (pinfunction "04_04") (pintype "passive"))
      (node (ref "JP1") (pin "26") (pinfunction "26_26") (pintype "passive"))
      (node (ref "JP4") (pin "3") (pinfunction "3_3") (pintype "passive"))
      (node (ref "JP4") (pin "4") (pinfunction "4_4") (pintype "passive"))
      (node (ref "SW5") (pin "1") (pinfunction "P_1") (pintype "passive"))
      (node (ref "SW6") (pin "1") (pinfunction "P_1") (pintype "passive"))
      (node (ref "SW7") (pin "1") (pinfunction "P_1") (pintype "passive"))
      (node (ref "SW8") (pin "1") (pinfunction "P_1") (pintype "passive"))
    )
    (net (code "81") (name "RF2") (class "Default")
      (node (ref "JP1") (pin "27") (pinfunction "27_27") (pintype "passive"))
      (node (ref "SW10") (pin "1") (pinfunction "P_1") (pintype "passive"))
      (node (ref "SW11") (pin "1") (pinfunction "P_1") (pintype "passive"))
      (node (ref "SW12") (pin "1") (pinfunction "P_1") (pintype "passive"))
      (node (ref "SW9") (pin "1") (pinfunction "P_1") (pintype "passive"))
    )
    (net (code "82") (name "RF3") (class "Default")
      (node (ref "JP1") (pin "28") (pinfunction "28_28") (pintype "passive"))
      (node (ref "SW13") (pin "1") (pinfunction "P_1") (pintype "passive"))
      (node (ref "SW14") (pin "1") (pinfunction "P_1") (pintype "passive"))
      (node (ref "SW15") (pin "1") (pinfunction "P_1") (pintype "passive"))
      (node (ref "SW16") (pin "1") (pinfunction "P_1") (pintype "passive"))
    )
    (net (code "83") (name "RF4") (class "Default")
      (node (ref "JP2") (pin "23") (pinfunction "23_23") (pintype "passive"))
      (node (ref "R24") (pin "2") (pinfunction "2_2") (pintype "passive"))
      (node (ref "SW1") (pin "2") (pinfunction "S_2") (pintype "passive"))
      (node (ref "SW13") (pin "2") (pinfunction "S_2") (pintype "passive"))
      (node (ref "SW5") (pin "2") (pinfunction "S_2") (pintype "passive"))
      (node (ref "SW9") (pin "2") (pinfunction "S_2") (pintype "passive"))
    )
    (net (code "84") (name "RF5") (class "Default")
      (node (ref "JP2") (pin "22") (pinfunction "22_22") (pintype "passive"))
      (node (ref "R25") (pin "2") (pinfunction "2_2") (pintype "passive"))
      (node (ref "SW10") (pin "2") (pinfunction "S_2") (pintype "passive"))
      (node (ref "SW14") (pin "2") (pinfunction "S_2") (pintype "passive"))
      (node (ref "SW2") (pin "2") (pinfunction "S_2") (pintype "passive"))
      (node (ref "SW6") (pin "2") (pinfunction "S_2") (pintype "passive"))
    )
    (net (code "85") (name "RF6") (class "Default")
      (node (ref "JP2") (pin "21") (pinfunction "21_21") (pintype "passive"))
      (node (ref "R26") (pin "2") (pinfunction "2_2") (pintype "passive"))
      (node (ref "SW11") (pin "2") (pinfunction "S_2") (pintype "passive"))
      (node (ref "SW15") (pin "2") (pinfunction "S_2") (pintype "passive"))
      (node (ref "SW3") (pin "2") (pinfunction "S_2") (pintype "passive"))
      (node (ref "SW7") (pin "2") (pinfunction "S_2") (pintype "passive"))
    )
    (net (code "86") (name "RF7") (class "Default")
      (node (ref "JP2") (pin "20") (pinfunction "20_20") (pintype "passive"))
      (node (ref "R27") (pin "2") (pinfunction "2_2") (pintype "passive"))
      (node (ref "SW12") (pin "2") (pinfunction "S_2") (pintype "passive"))
      (node (ref "SW16") (pin "2") (pinfunction "S_2") (pintype "passive"))
      (node (ref "SW4") (pin "2") (pinfunction "S_2") (pintype "passive"))
      (node (ref "SW8") (pin "2") (pinfunction "S_2") (pintype "passive"))
    )
    (net (code "87") (name "VBUS") (class "Default")
      (node (ref "JP2") (pin "01") (pinfunction "01_01") (pintype "passive"))
      (node (ref "LCD1") (pin "2") (pinfunction "VDD_2") (pintype "power_in"))
      (node (ref "R13") (pin "1") (pinfunction "1_1") (pintype "passive"))
      (node (ref "R14") (pin "1") (pinfunction "1_1") (pintype "passive"))
    )
    (net (code "88") (name "VO") (class "Default")
      (node (ref "LCD1") (pin "3") (pinfunction "VO_3") (pintype "bidirectional"))
      (node (ref "R14") (pin "2") (pinfunction "2_2") (pintype "passive"))
    )
    (net (code "89") (name "VTG") (class "Default")
      (node (ref "IC1") (pin "10") (pinfunction "COM_10") (pintype "passive"))
      (node (ref "JP2") (pin "06") (pinfunction "06_06") (pintype "passive"))
      (node (ref "JP4") (pin "25") (pinfunction "25_25") (pintype "passive"))
      (node (ref "JP4") (pin "26") (pinfunction "26_26") (pintype "passive"))
      (node (ref "R24") (pin "1") (pinfunction "1_1") (pintype "passive"))
      (node (ref "R25") (pin "1") (pinfunction "1_1") (pintype "passive"))
      (node (ref "R26") (pin "1") (pinfunction "1_1") (pintype "passive"))
      (node (ref "R27") (pin "1") (pinfunction "1_1") (pintype "passive"))
      (node (ref "TEMP") (pin "1") (pinfunction "+VS_1") (pintype "power_in"))
    )
    (net (code "90") (name "unconnected-(SW1-P1-Pad3)") (class "Default")
      (node (ref "SW1") (pin "3") (pinfunction "P1_3") (pintype "passive"))
    )
    (net (code "91") (name "unconnected-(SW1-S1-Pad4)") (class "Default")
      (node (ref "SW1") (pin "4") (pinfunction "S1_4") (pintype "passive"))
    )
    (net (code "92") (name "unconnected-(SW2-P1-Pad3)") (class "Default")
      (node (ref "SW2") (pin "3") (pinfunction "P1_3") (pintype "passive"))
    )
    (net (code "93") (name "unconnected-(SW2-S1-Pad4)") (class "Default")
      (node (ref "SW2") (pin "4") (pinfunction "S1_4") (pintype "passive"))
    )
    (net (code "94") (name "unconnected-(SW3-P1-Pad3)") (class "Default")
      (node (ref "SW3") (pin "3") (pinfunction "P1_3") (pintype "passive"))
    )
    (net (code "95") (name "unconnected-(SW3-S1-Pad4)") (class "Default")
      (node (ref "SW3") (pin "4") (pinfunction "S1_4") (pintype "passive"))
    )
    (net (code "96") (name "unconnected-(SW4-P1-Pad3)") (class "Default")
      (node (ref "SW4") (pin "3") (pinfunction "P1_3") (pintype "passive"))
    )
    (net (code "97") (name "unconnected-(SW4-S1-Pad4)") (class "Default")
      (node (ref "SW4") (pin "4") (pinfunction "S1_4") (pintype "passive"))
    )
    (net (code "98") (name "unconnected-(SW5-P1-Pad3)") (class "Default")
      (node (ref "SW5") (pin "3") (pinfunction "P1_3") (pintype "passive"))
    )
    (net (code "99") (name "unconnected-(SW5-S1-Pad4)") (class "Default")
      (node (ref "SW5") (pin "4") (pinfunction "S1_4") (pintype "passive"))
    )
    (net (code "100") (name "unconnected-(SW6-P1-Pad3)") (class "Default")
      (node (ref "SW6") (pin "3") (pinfunction "P1_3") (pintype "passive"))
    )
    (net (code "101") (name "unconnected-(SW6-S1-Pad4)") (class "Default")
      (node (ref "SW6") (pin "4") (pinfunction "S1_4") (pintype "passive"))
    )
    (net (code "102") (name "unconnected-(SW7-P1-Pad3)") (class "Default")
      (node (ref "SW7") (pin "3") (pinfunction "P1_3") (pintype "passive"))
    )
    (net (code "103") (name "unconnected-(SW7-S1-Pad4)") (class "Default")
      (node (ref "SW7") (pin "4") (pinfunction "S1_4") (pintype "passive"))
    )
    (net (code "104") (name "unconnected-(SW8-P1-Pad3)") (class "Default")
      (node (ref "SW8") (pin "3") (pinfunction "P1_3") (pintype "passive"))
    )
    (net (code "105") (name "unconnected-(SW8-S1-Pad4)") (class "Default")
      (node (ref "SW8") (pin "4") (pinfunction "S1_4") (pintype "passive"))
    )
    (net (code "106") (name "unconnected-(SW9-P1-Pad3)") (class "Default")
      (node (ref "SW9") (pin "3") (pinfunction "P1_3") (pintype "passive"))
    )
    (net (code "107") (name "unconnected-(SW9-S1-Pad4)") (class "Default")
      (node (ref "SW9") (pin "4") (pinfunction "S1_4") (pintype "passive"))
    )
    (net (code "108") (name "unconnected-(SW10-P1-Pad3)") (class "Default")
      (node (ref "SW10") (pin "3") (pinfunction "P1_3") (pintype "passive"))
    )
    (net (code "109") (name "unconnected-(SW10-S1-Pad4)") (class "Default")
      (node (ref "SW10") (pin "4") (pinfunction "S1_4") (pintype "passive"))
    )
    (net (code "110") (name "unconnected-(SW11-P1-Pad3)") (class "Default")
      (node (ref "SW11") (pin "3") (pinfunction "P1_3") (pintype "passive"))
    )
    (net (code "111") (name "unconnected-(SW11-S1-Pad4)") (class "Default")
      (node (ref "SW11") (pin "4") (pinfunction "S1_4") (pintype "passive"))
    )
    (net (code "112") (name "unconnected-(SW12-P1-Pad3)") (class "Default")
      (node (ref "SW12") (pin "3") (pinfunction "P1_3") (pintype "passive"))
    )
    (net (code "113") (name "unconnected-(SW12-S1-Pad4)") (class "Default")
      (node (ref "SW12") (pin "4") (pinfunction "S1_4") (pintype "passive"))
    )
    (net (code "114") (name "unconnected-(SW13-P1-Pad3)") (class "Default")
      (node (ref "SW13") (pin "3") (pinfunction "P1_3") (pintype "passive"))
    )
    (net (code "115") (name "unconnected-(SW13-S1-Pad4)") (class "Default")
      (node (ref "SW13") (pin "4") (pinfunction "S1_4") (pintype "passive"))
    )
    (net (code "116") (name "unconnected-(SW14-P1-Pad3)") (class "Default")
      (node (ref "SW14") (pin "3") (pinfunction "P1_3") (pintype "passive"))
    )
    (net (code "117") (name "unconnected-(SW14-S1-Pad4)") (class "Default")
      (node (ref "SW14") (pin "4") (pinfunction "S1_4") (pintype "passive"))
    )
    (net (code "118") (name "unconnected-(SW15-P1-Pad3)") (class "Default")
      (node (ref "SW15") (pin "3") (pinfunction "P1_3") (pintype "passive"))
    )
    (net (code "119") (name "unconnected-(SW15-S1-Pad4)") (class "Default")
      (node (ref "SW15") (pin "4") (pinfunction "S1_4") (pintype "passive"))
    )
    (net (code "120") (name "unconnected-(SW16-P1-Pad3)") (class "Default")
      (node (ref "SW16") (pin "3") (pinfunction "P1_3") (pintype "passive"))
    )
    (net (code "121") (name "unconnected-(SW16-S1-Pad4)") (class "Default")
      (node (ref "SW16") (pin "4") (pinfunction "S1_4") (pintype "passive"))
    )
  )
)
